# STM32WB09.net
KiCad netlist of a schematic drawn in Altium Designer
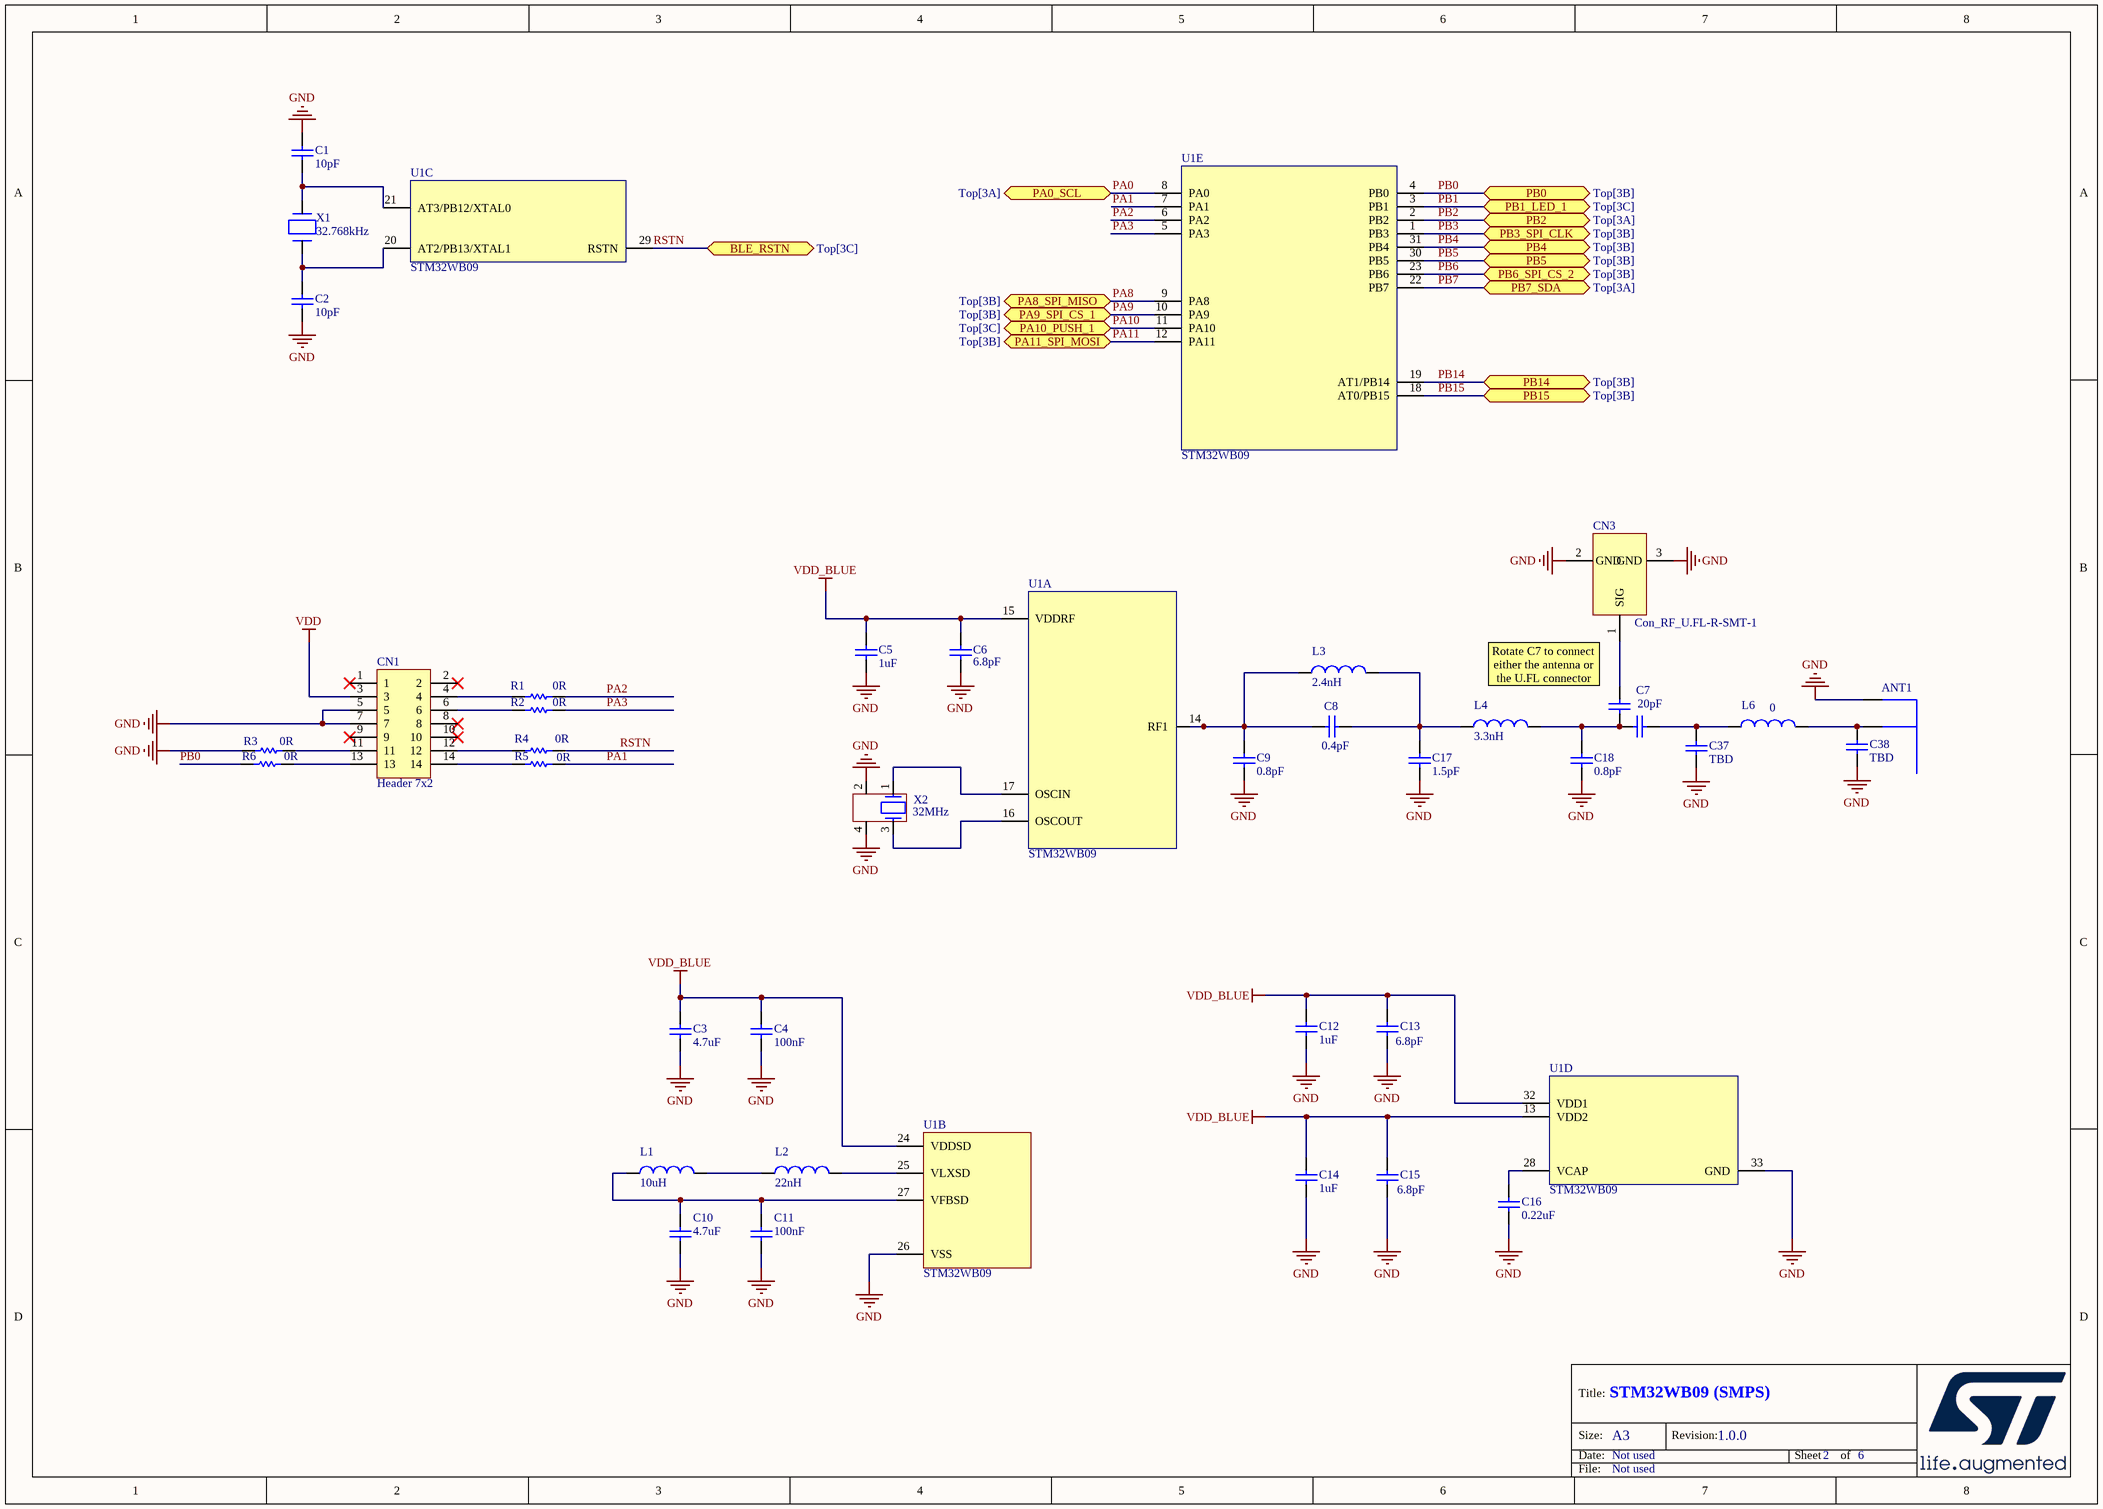
[diagram p0: STM32WB09.SchDoc]

(export (version "E")
  (design (tool "Eeschema 10.0.6"))
  (components
    (comp (ref "ANT1")
      (value "BLE_ANT")
      (footprint "ANTENNA_F")
      (description "2.4 GHz PIFA")
      (libsource (lib "missing_parts") (part "BLE_ANT"))
    )
    (comp (ref "C1")
      (value "10pF")
      (footprint "C0402")
      (description "Capacitor, MLCC, 10pF, 50V, NPO, +/-5%, 0402, T=0.5mm")
      (fields (field (name "INTERNAL_PART_NUMBER") "MCD-00015") (field (name "MANUFACTURER") "YAGEO"))
      (libsource (lib "MCD_PARTS_database") (part "Capacitor"))
    )
    (comp (ref "C2")
      (value "10pF")
      (footprint "C0402")
      (description "Capacitor, MLCC, 10pF, 50V, NPO, +/-5%, 0402, T=0.5mm")
      (fields (field (name "INTERNAL_PART_NUMBER") "MCD-00015") (field (name "MANUFACTURER") "YAGEO"))
      (libsource (lib "MCD_PARTS_database") (part "Capacitor"))
    )
    (comp (ref "C3")
      (value "4.7uF")
      (footprint "C0402")
      (description "Capacitor, MLCC, 4.7uF, X5R, 10V, +/-20%, 0402, T=0.5mm")
      (fields (field (name "INTERNAL_PART_NUMBER") "MCD-03431") (field (name "MANUFACTURER") "MURATA"))
      (libsource (lib "MCD_PARTS_database") (part "Capacitor"))
    )
    (comp (ref "C4")
      (value "100nF")
      (footprint "C0201_H0P3")
      (description "Capacitor, MLCC,100nF, 10V, X5R, +/-10%, 0201, T=0.3mm")
      (fields (field (name "INTERNAL_PART_NUMBER") "MCD-01535") (field (name "MANUFACTURER") "MURATA"))
      (libsource (lib "MCD_PARTS_database") (part "Capacitor"))
    )
    (comp (ref "C5")
      (value "1uF")
      (footprint "C0402")
      (description "Capacitor, MLCC, 1uF, X7R, 6.3V,+/- 10%, 0402, T=0.5mm")
      (fields (field (name "INTERNAL_PART_NUMBER") "MCD-03432") (field (name "MANUFACTURER") "MURATA"))
      (libsource (lib "MCD_PARTS_database") (part "Capacitor"))
    )
    (comp (ref "C6")
      (value "6.8pF")
      (footprint "C0201_H0P3")
      (description "Cap Ceramic 6.8pF 25V C0G 0.25pF SMD 0201 125°C Paper T/R")
      (fields
        (field (name "MANUFACTURER") "Murata")
        (field (name "MANUFACTURER PART NUMBER") "GJM0335C1E6R8CB01D")
      )
      (libsource (lib "MCD_PARTS_database") (part "Capacitor"))
    )
    (comp (ref "C7")
      (value "20pF")
      (footprint "SMD 0201 DEV")
      (description "Cap Ceramic 20pF 25V C0G 2% Pad SMD 0201 125C T/R")
      (fields
        (field (name "MANUFACTURER") "Murata")
        (field (name "MANUFACTURER PART NUMBER") "GJM0335C1E200GB01D")
      )
      (libsource (lib "missing_parts") (part "C_0201_DEV"))
    )
    (comp (ref "C8")
      (value "0.4pF")
      (footprint "0_5p_capacitor_SMD_0201")
      (description "0201 0.4 pF 25 V ±0.05 pF Tolerance C0G SMT Multilayer Ceramic Capacitor")
      (fields
        (field (name "MANUFACTURER") "Murata")
        (field (name "MANUFACTURER PART NUMBER") "GJM0335C1ER40WB01D")
      )
      (libsource (lib "missing_parts") (part "MCD-02284_2"))
    )
    (comp (ref "C9")
      (value "0.8pF")
      (footprint "0_8p_capacitor_SMD_0201")
      (description "Multilayer Ceramic Capacitor, 0.8 pF, 25 V, ± 0.05pF, C0G (NP0), 0201 [0603 Metric]")
      (fields
        (field (name "MANUFACTURER") "Murata")
        (field (name "MANUFACTURER PART NUMBER") "GJM0335C1ER80WB01D")
      )
      (libsource (lib "missing_parts") (part "MCD-02284_1"))
    )
    (comp (ref "C10")
      (value "4.7uF")
      (footprint "C0402")
      (description "Capacitor, MLCC, 4.7uF, X5R, 10V, +/-20%, 0402, T=0.5mm")
      (fields (field (name "INTERNAL_PART_NUMBER") "MCD-03431") (field (name "MANUFACTURER") "MURATA"))
      (libsource (lib "MCD_PARTS_database") (part "Capacitor"))
    )
    (comp (ref "C11")
      (value "100nF")
      (footprint "C0402")
      (description "Capacitor, MLCC, 100nF, +/-10%, X7R, 25V, 0402, T=0.5mm")
      (fields (field (name "INTERNAL_PART_NUMBER") "MCD-03442") (field (name "MANUFACTURER") "MURATA"))
      (libsource (lib "MCD_PARTS_database") (part "Capacitor"))
    )
    (comp (ref "C12")
      (value "1uF")
      (footprint "C0402")
      (description "Capacitor, MLCC, 1uF, X7R, 6.3V,+/- 10%, 0402, T=0.5mm")
      (fields (field (name "INTERNAL_PART_NUMBER") "MCD-03432") (field (name "MANUFACTURER") "MURATA"))
      (libsource (lib "MCD_PARTS_database") (part "Capacitor"))
    )
    (comp (ref "C13")
      (value "6.8pF")
      (footprint "C0201_H0P3")
      (description "Cap Ceramic 6.8pF 25V C0G 0.25pF SMD 0201 125°C Paper T/R")
      (fields
        (field (name "MANUFACTURER") "Murata")
        (field (name "MANUFACTURER PART NUMBER") "GJM0335C1E6R8CB01D")
      )
      (libsource (lib "MCD_PARTS_database") (part "Capacitor"))
    )
    (comp (ref "C14")
      (value "1uF")
      (footprint "C0402")
      (description "Capacitor, MLCC, 1uF, X7R, 6.3V,+/- 10%, 0402, T=0.5mm")
      (fields (field (name "INTERNAL_PART_NUMBER") "MCD-03432") (field (name "MANUFACTURER") "MURATA"))
      (libsource (lib "MCD_PARTS_database") (part "Capacitor"))
    )
    (comp (ref "C15")
      (value "6.8pF")
      (footprint "C0201_H0P3")
      (description "Cap Ceramic 6.8pF 25V C0G 0.25pF SMD 0201 125°C Paper T/R")
      (fields
        (field (name "MANUFACTURER") "Murata")
        (field (name "MANUFACTURER PART NUMBER") "GJM0335C1E6R8CB01D")
      )
      (libsource (lib "MCD_PARTS_database") (part "Capacitor"))
    )
    (comp (ref "C16")
      (value "0.22uF")
      (footprint "C0402")
      (description "Capacitor, MLCC, 0.22uF, X5R, 6.3V, +/-10%, 0402, T=0.5mm")
      (fields (field (name "INTERNAL_PART_NUMBER") "MCD-03483") (field (name "MANUFACTURER") "YAGEO"))
      (libsource (lib "MCD_PARTS_database") (part "Capacitor"))
    )
    (comp (ref "C17")
      (value "1.5pF")
      (footprint "1_5p_capacitor_SMD_0201")
      (description "Multilayer Ceramic Capacitor, 1.5 pF, 25 V, ± 0.1pF, C0G (NP0), 0201 [0603 Metric]")
      (fields
        (field (name "MANUFACTURER") "Murata")
        (field (name "MANUFACTURER PART NUMBER") "GJM0335C1E1R5BB01D")
      )
      (libsource (lib "missing_parts") (part "MCD-02284_3"))
    )
    (comp (ref "C18")
      (value "0.8pF")
      (footprint "0_8p_capacitor_SMD_0201")
      (description "Multilayer Ceramic Capacitor, 0.8 pF, 25 V, ± 0.05pF, C0G (NP0), 0201 [0603 Metric]")
      (fields
        (field (name "MANUFACTURER") "Murata")
        (field (name "MANUFACTURER PART NUMBER") "GJM0335C1ER80WB01D")
      )
      (libsource (lib "missing_parts") (part "MCD-02284_1"))
    )
    (comp (ref "C37")
      (value "TBD")
      (footprint "1_5p_capacitor_SMD_0201")
      (description "Multilayer Ceramic Capacitor, 1.5 pF, 25 V, ± 0.1pF, C0G (NP0), 0201 [0603 Metric]")
      (fields
        (field (name "MANUFACTURER") "Murata")
        (field (name "MANUFACTURER PART NUMBER") "GJM0335C1E1R5BB01D")
      )
      (libsource (lib "missing_parts") (part "MCD-02284_3"))
    )
    (comp (ref "C38")
      (value "TBD")
      (footprint "0_8p_capacitor_SMD_0201")
      (description "Multilayer Ceramic Capacitor, 0.8 pF, 25 V, ± 0.05pF, C0G (NP0), 0201 [0603 Metric]")
      (fields
        (field (name "MANUFACTURER") "Murata")
        (field (name "MANUFACTURER PART NUMBER") "GJM0335C1ER80WB01D")
      )
      (libsource (lib "missing_parts") (part "MCD-02284_1"))
    )
    (comp (ref "CN1")
      (value "Header 7x2")
      (footprint "CON_STDC14_Receiver_SMALL")
      (description "Header, 7x2, 1.27mm, VR, SMD, T=5.97mm")
      (fields (field (name "INTERNAL_PART_NUMBER") "MCD-00639") (field (name "MANUFACTURER") "SAMTEC"))
      (libsource (lib "MCD_PARTS_database") (part "Header 7x2"))
    )
    (comp (ref "CN3")
      (value "Con_RF_U.FL-R-SMT-1")
      (footprint "CON_HRS_U.FL-R-SMT-1")
      (description "Connector_RF, 0Hz to 6GHz, 50R, VR, SMD, T= 1.25mm")
      (fields (field (name "INTERNAL_PART_NUMBER") "MCD-01583") (field (name "BMS_PART_NUMBER") "9187005"))
      (libsource (lib "MCD_PARTS_database") (part "U.FL-R-SMT-1"))
    )
    (comp (ref "L1")
      (value "10uH")
      (footprint "IND_0805_MURATA_LQM21")
      (description "Inductor, MLCC, 10uH, +/-20%, 300mA, 845mR, 0805, T=1.45mm")
      (fields (field (name "INTERNAL_PART_NUMBER") "MCD-03438") (field (name "MANUFACTURER") "MURATA"))
      (libsource (lib "MCD_PARTS_database") (part "Inductor"))
    )
    (comp (ref "L2")
      (value "22nH")
      (footprint "C0402")
      (description "Inductor, MLCC, 22nH, +/-2%, 350mA, 0.58R, 0402, T=1.45mm")
      (fields (field (name "INTERNAL_PART_NUMBER") "MCD-03439") (field (name "MANUFACTURER") "MURATA"))
      (libsource (lib "MCD_PARTS_database") (part "Inductor"))
    )
    (comp (ref "L3")
      (value "2.4nH")
      (footprint "2n4_inductor_SMD_0201")
      (description "Inductor RF Chip Thin Film 2.4nH 0.1nH 500MHz 14Q-Factor 500mA 200mOhm DCR 0201 Paper T/R")
      (fields
        (field (name "MANUFACTURER") "Murata")
        (field (name "MANUFACTURER PART NUMBER") "LQP03TN2N4B02D")
      )
      (libsource (lib "missing_parts") (part "MCD-03552"))
    )
    (comp (ref "L4")
      (value "3.3nH")
      (footprint "3n3_inductor_SMD_0201")
      (description "Inductor RF Chip Thin Film 3.3nH 0.1nH 500MHz 14Q-Factor 450mA 250mOhm DCR 0201 Paper T/R")
      (fields
        (field (name "MANUFACTURER") "Murata")
        (field (name "MANUFACTURER PART NUMBER") "LQP03TN3N3B02D")
      )
      (libsource (lib "missing_parts") (part "MCD-03552_1"))
    )
    (comp (ref "L6")
      (value "0")
      (footprint "3n3_inductor_SMD_0201")
      (description "0201 0 ohm")
      (fields (field (name "Comment") "Inductor"))
      (libsource (lib "missing_parts") (part "MCD-03552_1"))
    )
    (comp (ref "R1")
      (value "0R")
      (footprint "R0402")
      (description "Resistor, 0R, 0402, +/-5%, 1/16W")
      (fields (field (name "INTERNAL_PART_NUMBER") "MCD-00052") (field (name "MANUFACTURER") "YAGEO"))
      (libsource (lib "MCD_PARTS_database") (part "Resistor"))
    )
    (comp (ref "R2")
      (value "0R")
      (footprint "R0402")
      (description "Resistor, 0R, 0402, +/-5%, 1/16W")
      (fields (field (name "INTERNAL_PART_NUMBER") "MCD-00052") (field (name "MANUFACTURER") "YAGEO"))
      (libsource (lib "MCD_PARTS_database") (part "Resistor"))
    )
    (comp (ref "R3")
      (value "0R")
      (footprint "R0402")
      (description "Resistor, 0R, 0402, +/-5%, 1/16W")
      (fields (field (name "INTERNAL_PART_NUMBER") "MCD-00052") (field (name "MANUFACTURER") "YAGEO"))
      (libsource (lib "MCD_PARTS_database") (part "Resistor"))
    )
    (comp (ref "R4")
      (value "0R")
      (footprint "R0402")
      (description "Resistor, 0R, 0402, +/-5%, 1/16W")
      (fields (field (name "INTERNAL_PART_NUMBER") "MCD-00052") (field (name "MANUFACTURER") "YAGEO"))
      (libsource (lib "MCD_PARTS_database") (part "Resistor"))
    )
    (comp (ref "R5")
      (value "0R")
      (footprint "R0402")
      (description "Resistor, 0R, 0402, +/-5%, 1/16W")
      (fields (field (name "INTERNAL_PART_NUMBER") "MCD-00052") (field (name "MANUFACTURER") "YAGEO"))
      (libsource (lib "MCD_PARTS_database") (part "Resistor"))
    )
    (comp (ref "R6")
      (value "0R")
      (footprint "R0402")
      (description "Resistor, 0R, 0402, +/-5%, 1/16W")
      (fields (field (name "INTERNAL_PART_NUMBER") "MCD-00052") (field (name "MANUFACTURER") "YAGEO"))
      (libsource (lib "MCD_PARTS_database") (part "Resistor"))
    )
    (comp (ref "U1")
      (value "STM32WB09")
      (footprint "ICC_QFN32-EPAD_5X5_P050")
      (description "Bluetooth® Low Energy wireless SoC")
      (fields
        (field (name "INTERNAL_PART_NUMBER") "MCD-03444")
        (field (name "MANUFACTURER") "STMICROELECTRONICS")
      )
      (libsource (lib "MCD_PARTS_database") (part "STM32WB09"))
    )
    (comp (ref "X1")
      (value "32.768kHz")
      (footprint "CRY_NX2012SA_2P")
      (description "Crystal, 32.768kHz, 7pF, +/-20ppm, 80K, 2.05x1.2mm")
      (fields (field (name "INTERNAL_PART_NUMBER") "MCD-01445") (field (name "BMS_PART_NUMBER") "9157043"))
      (libsource (lib "MCD_PARTS_database") (part "XTAL_2_PINS"))
    )
    (comp (ref "X2")
      (value "32MHz")
      (footprint "CRY_NX2016SA_4P")
      (description "Crystal, 32MHz, 8pF, +/-10ppm, 60R, 2x1.6mm")
      (fields (field (name "INTERNAL_PART_NUMBER") "MCD-01446") (field (name "BMS_PART_NUMBER") "9157042"))
      (libsource (lib "MCD_PARTS_database") (part "XTAL_4_PINS"))
    )
  )
  (nets
    (net (code "1") (name "/PA0") (class "Default")
      (node (ref "U1") (pin "8") (pinfunction "PA0_8") (pintype "passive"))
    )
    (net (code "2") (name "/PA1") (class "Default")
      (node (ref "R5") (pin "2") (pinfunction "2_2") (pintype "passive"))
      (node (ref "U1") (pin "7") (pinfunction "PA1_7") (pintype "passive"))
    )
    (net (code "3") (name "/PA2") (class "Default")
      (node (ref "R1") (pin "2") (pinfunction "2_2") (pintype "passive"))
      (node (ref "U1") (pin "6") (pinfunction "PA2_6") (pintype "passive"))
    )
    (net (code "4") (name "/PA3") (class "Default")
      (node (ref "R2") (pin "2") (pinfunction "2_2") (pintype "passive"))
      (node (ref "U1") (pin "5") (pinfunction "PA3_5") (pintype "passive"))
    )
    (net (code "5") (name "/PA8") (class "Default")
      (node (ref "U1") (pin "9") (pinfunction "PA8_9") (pintype "passive"))
    )
    (net (code "6") (name "/PA9") (class "Default")
      (node (ref "U1") (pin "10") (pinfunction "PA9_10") (pintype "passive"))
    )
    (net (code "7") (name "/PA10") (class "Default")
      (node (ref "U1") (pin "11") (pinfunction "PA10_11") (pintype "passive"))
    )
    (net (code "8") (name "/PA11") (class "Default")
      (node (ref "U1") (pin "12") (pinfunction "PA11_12") (pintype "passive"))
    )
    (net (code "9") (name "/PB0") (class "Default")
      (node (ref "R6") (pin "1") (pinfunction "1_1") (pintype "passive"))
      (node (ref "U1") (pin "4") (pinfunction "PB0_4") (pintype "passive"))
    )
    (net (code "10") (name "/PB1") (class "Default")
      (node (ref "U1") (pin "3") (pinfunction "PB1_3") (pintype "passive"))
    )
    (net (code "11") (name "/PB2") (class "Default")
      (node (ref "U1") (pin "2") (pinfunction "PB2_2") (pintype "passive"))
    )
    (net (code "12") (name "/PB3") (class "Default")
      (node (ref "U1") (pin "1") (pinfunction "PB3_1") (pintype "passive"))
    )
    (net (code "13") (name "/PB4") (class "Default")
      (node (ref "U1") (pin "31") (pinfunction "PB4_31") (pintype "passive"))
    )
    (net (code "14") (name "/PB5") (class "Default")
      (node (ref "U1") (pin "30") (pinfunction "PB5_30") (pintype "passive"))
    )
    (net (code "15") (name "/PB6") (class "Default")
      (node (ref "U1") (pin "23") (pinfunction "PB6_23") (pintype "passive"))
    )
    (net (code "16") (name "/PB7") (class "Default")
      (node (ref "U1") (pin "22") (pinfunction "PB7_22") (pintype "passive"))
    )
    (net (code "17") (name "/PB14") (class "Default")
      (node (ref "U1") (pin "19") (pinfunction "AT1/PB14_19") (pintype "passive"))
    )
    (net (code "18") (name "/PB15") (class "Default")
      (node (ref "U1") (pin "18") (pinfunction "AT0/PB15_18") (pintype "passive"))
    )
    (net (code "19") (name "/RSTN") (class "Default")
      (node (ref "R4") (pin "2") (pinfunction "2_2") (pintype "passive"))
      (node (ref "U1") (pin "29") (pinfunction "RSTN_29") (pintype "passive"))
    )
    (net (code "20") (name "GND") (class "Default")
      (node (ref "ANT1") (pin "2") (pinfunction "2_2") (pintype "passive"))
      (node (ref "C1") (pin "2") (pinfunction "2_2") (pintype "passive"))
      (node (ref "C10") (pin "1") (pinfunction "1_1") (pintype "passive"))
      (node (ref "C11") (pin "1") (pinfunction "1_1") (pintype "passive"))
      (node (ref "C12") (pin "1") (pinfunction "1_1") (pintype "passive"))
      (node (ref "C13") (pin "1") (pinfunction "1_1") (pintype "passive"))
      (node (ref "C14") (pin "1") (pinfunction "1_1") (pintype "passive"))
      (node (ref "C15") (pin "1") (pinfunction "1_1") (pintype "passive"))
      (node (ref "C16") (pin "1") (pinfunction "1_1") (pintype "passive"))
      (node (ref "C17") (pin "1") (pinfunction "1_1") (pintype "passive"))
      (node (ref "C18") (pin "1") (pinfunction "1_1") (pintype "passive"))
      (node (ref "C2") (pin "1") (pinfunction "1_1") (pintype "passive"))
      (node (ref "C3") (pin "1") (pinfunction "1_1") (pintype "passive"))
      (node (ref "C37") (pin "1") (pinfunction "1_1") (pintype "passive"))
      (node (ref "C38") (pin "1") (pinfunction "1_1") (pintype "passive"))
      (node (ref "C4") (pin "1") (pinfunction "1_1") (pintype "passive"))
      (node (ref "C5") (pin "1") (pinfunction "1_1") (pintype "passive"))
      (node (ref "C6") (pin "1") (pinfunction "1_1") (pintype "passive"))
      (node (ref "C9") (pin "1") (pinfunction "1_1") (pintype "passive"))
      (node (ref "CN1") (pin "5") (pinfunction "5_5") (pintype "passive"))
      (node (ref "CN1") (pin "7") (pinfunction "7_7") (pintype "passive"))
      (node (ref "CN3") (pin "2") (pinfunction "GND_2") (pintype "passive"))
      (node (ref "CN3") (pin "3") (pinfunction "GND_3") (pintype "passive"))
      (node (ref "R3") (pin "1") (pinfunction "1_1") (pintype "passive"))
      (node (ref "U1") (pin "26") (pinfunction "VSS_26") (pintype "passive"))
      (node (ref "U1") (pin "33") (pinfunction "GND_33") (pintype "passive"))
      (node (ref "X2") (pin "2") (pinfunction "2_2") (pintype "passive"))
      (node (ref "X2") (pin "4") (pinfunction "4_4") (pintype "passive"))
    )
    (net (code "21") (name "Net-(ANT1-Pad1)") (class "Default")
      (node (ref "ANT1") (pin "1") (pinfunction "1_1") (pintype "passive"))
      (node (ref "C38") (pin "2") (pinfunction "2_2") (pintype "passive"))
      (node (ref "L6") (pin "2") (pinfunction "2_2") (pintype "passive"))
    )
    (net (code "22") (name "Net-(C17-Pad2)") (class "Default")
      (node (ref "C17") (pin "2") (pinfunction "2_2") (pintype "passive"))
      (node (ref "C8") (pin "2") (pinfunction "2_2") (pintype "passive"))
      (node (ref "L3") (pin "2") (pinfunction "2_2") (pintype "passive"))
      (node (ref "L4") (pin "1") (pinfunction "1_1") (pintype "passive"))
    )
    (net (code "23") (name "Net-(C18-Pad2)") (class "Default")
      (node (ref "C18") (pin "2") (pinfunction "2_2") (pintype "passive"))
      (node (ref "C7") (pin "1") (pinfunction "1_1") (pintype "passive"))
      (node (ref "L4") (pin "2") (pinfunction "2_2") (pintype "passive"))
    )
    (net (code "24") (name "Net-(C37-Pad2)") (class "Default")
      (node (ref "C37") (pin "2") (pinfunction "2_2") (pintype "passive"))
      (node (ref "C7") (pin "3") (pinfunction "3_3") (pintype "passive"))
      (node (ref "L6") (pin "1") (pinfunction "1_1") (pintype "passive"))
    )
    (net (code "25") (name "Net-(CN1-Pad4)") (class "Default")
      (node (ref "CN1") (pin "4") (pinfunction "4_4") (pintype "passive"))
      (node (ref "R1") (pin "1") (pinfunction "1_1") (pintype "passive"))
    )
    (net (code "26") (name "Net-(CN1-Pad6)") (class "Default")
      (node (ref "CN1") (pin "6") (pinfunction "6_6") (pintype "passive"))
      (node (ref "R2") (pin "1") (pinfunction "1_1") (pintype "passive"))
    )
    (net (code "27") (name "Net-(CN1-Pad11)") (class "Default")
      (node (ref "CN1") (pin "11") (pinfunction "11_11") (pintype "passive"))
      (node (ref "R3") (pin "2") (pinfunction "2_2") (pintype "passive"))
    )
    (net (code "28") (name "Net-(CN1-Pad12)") (class "Default")
      (node (ref "CN1") (pin "12") (pinfunction "12_12") (pintype "passive"))
      (node (ref "R4") (pin "1") (pinfunction "1_1") (pintype "passive"))
    )
    (net (code "29") (name "Net-(CN1-Pad13)") (class "Default")
      (node (ref "CN1") (pin "13") (pinfunction "13_13") (pintype "passive"))
      (node (ref "R6") (pin "2") (pinfunction "2_2") (pintype "passive"))
    )
    (net (code "30") (name "Net-(CN1-Pad14)") (class "Default")
      (node (ref "CN1") (pin "14") (pinfunction "14_14") (pintype "passive"))
      (node (ref "R5") (pin "1") (pinfunction "1_1") (pintype "passive"))
    )
    (net (code "31") (name "Net-(CN3-SIG)") (class "Default")
      (node (ref "C7") (pin "2") (pinfunction "2_2") (pintype "passive"))
      (node (ref "CN3") (pin "1") (pinfunction "SIG_1") (pintype "passive"))
    )
    (net (code "32") (name "Net-(L1-Pad2)") (class "Default")
      (node (ref "L1") (pin "2") (pinfunction "2_2") (pintype "passive"))
      (node (ref "L2") (pin "1") (pinfunction "1_1") (pintype "passive"))
    )
    (net (code "33") (name "Net-(U1A-OSCIN)") (class "Default")
      (node (ref "U1") (pin "17") (pinfunction "OSCIN_17") (pintype "passive"))
      (node (ref "X2") (pin "1") (pinfunction "1_1") (pintype "passive"))
    )
    (net (code "34") (name "Net-(U1A-OSCOUT)") (class "Default")
      (node (ref "U1") (pin "16") (pinfunction "OSCOUT_16") (pintype "passive"))
      (node (ref "X2") (pin "3") (pinfunction "3_3") (pintype "passive"))
    )
    (net (code "35") (name "Net-(U1A-RF1)") (class "Default")
      (node (ref "C8") (pin "1") (pinfunction "1_1") (pintype "passive"))
      (node (ref "C9") (pin "2") (pinfunction "2_2") (pintype "passive"))
      (node (ref "L3") (pin "1") (pinfunction "1_1") (pintype "passive"))
      (node (ref "U1") (pin "14") (pinfunction "RF1_14") (pintype "passive"))
    )
    (net (code "36") (name "Net-(U1B-VFBSD)") (class "Default")
      (node (ref "C10") (pin "2") (pinfunction "2_2") (pintype "passive"))
      (node (ref "C11") (pin "2") (pinfunction "2_2") (pintype "passive"))
      (node (ref "L1") (pin "1") (pinfunction "1_1") (pintype "passive"))
      (node (ref "U1") (pin "27") (pinfunction "VFBSD_27") (pintype "passive"))
    )
    (net (code "37") (name "Net-(U1B-VLXSD)") (class "Default")
      (node (ref "L2") (pin "2") (pinfunction "2_2") (pintype "passive"))
      (node (ref "U1") (pin "25") (pinfunction "VLXSD_25") (pintype "passive"))
    )
    (net (code "38") (name "Net-(U1C-AT2{slash}PB13{slash}XTAL1)") (class "Default")
      (node (ref "C2") (pin "2") (pinfunction "2_2") (pintype "passive"))
      (node (ref "U1") (pin "20") (pinfunction "AT2/PB13/XTAL1_20") (pintype "passive"))
      (node (ref "X1") (pin "2") (pinfunction "X2_2") (pintype "passive"))
    )
    (net (code "39") (name "Net-(U1C-AT3{slash}PB12{slash}XTAL0)") (class "Default")
      (node (ref "C1") (pin "1") (pinfunction "1_1") (pintype "passive"))
      (node (ref "U1") (pin "21") (pinfunction "AT3/PB12/XTAL0_21") (pintype "passive"))
      (node (ref "X1") (pin "1") (pinfunction "X1_1") (pintype "passive"))
    )
    (net (code "40") (name "Net-(U1D-VCAP)") (class "Default")
      (node (ref "C16") (pin "2") (pinfunction "2_2") (pintype "passive"))
      (node (ref "U1") (pin "28") (pinfunction "VCAP_28") (pintype "passive"))
    )
    (net (code "41") (name "VDD") (class "Default")
      (node (ref "CN1") (pin "3") (pinfunction "3_3") (pintype "passive"))
    )
    (net (code "42") (name "VDD_BLUE") (class "Default")
      (node (ref "C12") (pin "2") (pinfunction "2_2") (pintype "passive"))
      (node (ref "C13") (pin "2") (pinfunction "2_2") (pintype "passive"))
      (node (ref "C14") (pin "2") (pinfunction "2_2") (pintype "passive"))
      (node (ref "C15") (pin "2") (pinfunction "2_2") (pintype "passive"))
      (node (ref "C3") (pin "2") (pinfunction "2_2") (pintype "passive"))
      (node (ref "C4") (pin "2") (pinfunction "2_2") (pintype "passive"))
      (node (ref "C5") (pin "2") (pinfunction "2_2") (pintype "passive"))
      (node (ref "C6") (pin "2") (pinfunction "2_2") (pintype "passive"))
      (node (ref "U1") (pin "13") (pinfunction "VDD2_13") (pintype "passive"))
      (node (ref "U1") (pin "15") (pinfunction "VDDRF_15") (pintype "passive"))
      (node (ref "U1") (pin "24") (pinfunction "VDDSD_24") (pintype "passive"))
      (node (ref "U1") (pin "32") (pinfunction "VDD1_32") (pintype "passive"))
    )
    (net (code "43") (name "unconnected-(CN1-Pad1)") (class "Default")
      (node (ref "CN1") (pin "1") (pinfunction "1_1") (pintype "passive+no_connect"))
    )
    (net (code "44") (name "unconnected-(CN1-Pad2)") (class "Default")
      (node (ref "CN1") (pin "2") (pinfunction "2_2") (pintype "passive+no_connect"))
    )
    (net (code "45") (name "unconnected-(CN1-Pad8)") (class "Default")
      (node (ref "CN1") (pin "8") (pinfunction "8_8") (pintype "passive+no_connect"))
    )
    (net (code "46") (name "unconnected-(CN1-Pad9)") (class "Default")
      (node (ref "CN1") (pin "9") (pinfunction "9_9") (pintype "passive+no_connect"))
    )
    (net (code "47") (name "unconnected-(CN1-Pad10)") (class "Default")
      (node (ref "CN1") (pin "10") (pinfunction "10_10") (pintype "passive+no_connect"))
    )
  )
)
